# Audio-Beamformer_HDMI_V1_0.net
KiCad netlist of a schematic drawn in Altium Designer
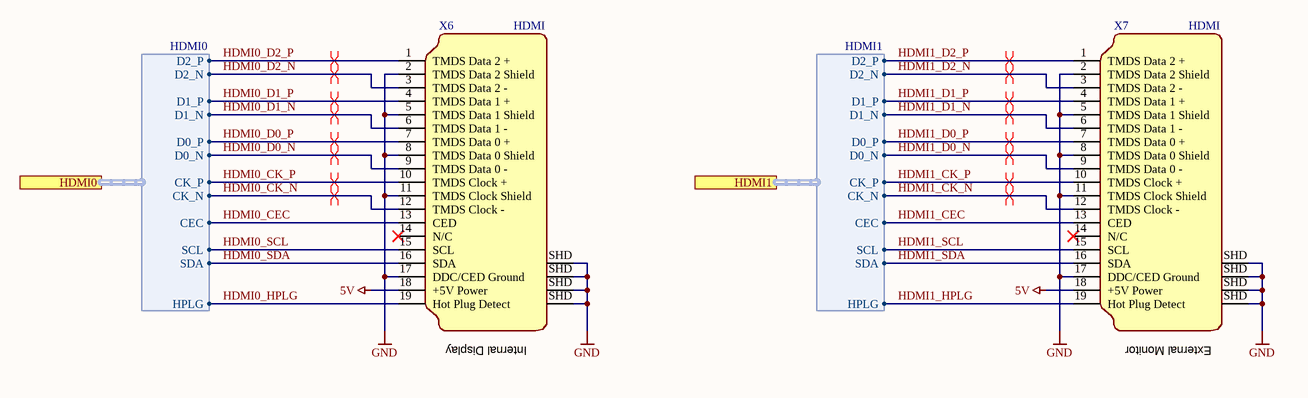
[diagram p0: Audio-Beamformer_HDMI_V1.0.SchDoc]

(export (version "E")
  (design (tool "Eeschema 10.0.6"))
  (components
    (comp (ref "X6")
      (value "HDMI")
      (footprint "SMD HDMI Horizontal")
      (description "Female Right Angle")
      (libsource (lib "Audio-Beamformer") (part "X-HDMI-Connector"))
    )
    (comp (ref "X7")
      (value "HDMI")
      (footprint "SMD HDMI Horizontal")
      (description "Female Right Angle")
      (libsource (lib "Audio-Beamformer") (part "X-HDMI-Connector"))
    )
  )
  (nets
    (net (code "3") (name "/HDMI0_CEC") (class "Default")
      (node (ref "X6") (pin "13") (pinfunction "CED_13") (pintype "passive"))
    )
    (net (code "4") (name "/HDMI0_CK_N") (class "Default")
      (node (ref "X6") (pin "12") (pinfunction "TMDS_Clock_-_12") (pintype "passive"))
    )
    (net (code "5") (name "/HDMI0_CK_P") (class "Default")
      (node (ref "X6") (pin "10") (pinfunction "TMDS_Clock_+_10") (pintype "passive"))
    )
    (net (code "6") (name "/HDMI0_D0_N") (class "Default")
      (node (ref "X6") (pin "9") (pinfunction "TMDS_Data_0_-_9") (pintype "passive"))
    )
    (net (code "7") (name "/HDMI0_D0_P") (class "Default")
      (node (ref "X6") (pin "7") (pinfunction "TMDS_Data_0_+_7") (pintype "passive"))
    )
    (net (code "8") (name "/HDMI0_D1_N") (class "Default")
      (node (ref "X6") (pin "6") (pinfunction "TMDS_Data_1_-_6") (pintype "passive"))
    )
    (net (code "9") (name "/HDMI0_D1_P") (class "Default")
      (node (ref "X6") (pin "4") (pinfunction "TMDS_Data_1_+_4") (pintype "passive"))
    )
    (net (code "10") (name "/HDMI0_D2_N") (class "Default")
      (node (ref "X6") (pin "3") (pinfunction "TMDS_Data_2_-_3") (pintype "passive"))
    )
    (net (code "11") (name "/HDMI0_D2_P") (class "Default")
      (node (ref "X6") (pin "1") (pinfunction "TMDS_Data_2_+_1") (pintype "passive"))
    )
    (net (code "12") (name "/HDMI0_HPLG") (class "Default")
      (node (ref "X6") (pin "19") (pinfunction "Hot_Plug_Detect_19") (pintype "passive"))
    )
    (net (code "13") (name "/HDMI0_SCL") (class "Default")
      (node (ref "X6") (pin "15") (pinfunction "SCL_15") (pintype "passive"))
    )
    (net (code "14") (name "/HDMI0_SDA") (class "Default")
      (node (ref "X6") (pin "16") (pinfunction "SDA_16") (pintype "passive"))
    )
    (net (code "15") (name "/HDMI1_CEC") (class "Default")
      (node (ref "X7") (pin "13") (pinfunction "CED_13") (pintype "passive"))
    )
    (net (code "16") (name "/HDMI1_CK_N") (class "Default")
      (node (ref "X7") (pin "12") (pinfunction "TMDS_Clock_-_12") (pintype "passive"))
    )
    (net (code "17") (name "/HDMI1_CK_P") (class "Default")
      (node (ref "X7") (pin "10") (pinfunction "TMDS_Clock_+_10") (pintype "passive"))
    )
    (net (code "18") (name "/HDMI1_D0_N") (class "Default")
      (node (ref "X7") (pin "9") (pinfunction "TMDS_Data_0_-_9") (pintype "passive"))
    )
    (net (code "19") (name "/HDMI1_D0_P") (class "Default")
      (node (ref "X7") (pin "7") (pinfunction "TMDS_Data_0_+_7") (pintype "passive"))
    )
    (net (code "20") (name "/HDMI1_D1_N") (class "Default")
      (node (ref "X7") (pin "6") (pinfunction "TMDS_Data_1_-_6") (pintype "passive"))
    )
    (net (code "21") (name "/HDMI1_D1_P") (class "Default")
      (node (ref "X7") (pin "4") (pinfunction "TMDS_Data_1_+_4") (pintype "passive"))
    )
    (net (code "22") (name "/HDMI1_D2_N") (class "Default")
      (node (ref "X7") (pin "3") (pinfunction "TMDS_Data_2_-_3") (pintype "passive"))
    )
    (net (code "23") (name "/HDMI1_D2_P") (class "Default")
      (node (ref "X7") (pin "1") (pinfunction "TMDS_Data_2_+_1") (pintype "passive"))
    )
    (net (code "24") (name "/HDMI1_HPLG") (class "Default")
      (node (ref "X7") (pin "19") (pinfunction "Hot_Plug_Detect_19") (pintype "passive"))
    )
    (net (code "25") (name "/HDMI1_SCL") (class "Default")
      (node (ref "X7") (pin "15") (pinfunction "SCL_15") (pintype "passive"))
    )
    (net (code "26") (name "/HDMI1_SDA") (class "Default")
      (node (ref "X7") (pin "16") (pinfunction "SDA_16") (pintype "passive"))
    )
    (net (code "29") (name "5V") (class "Default")
      (node (ref "X6") (pin "18") (pinfunction "+5V_Power_18") (pintype "passive"))
      (node (ref "X7") (pin "18") (pinfunction "+5V_Power_18") (pintype "passive"))
    )
    (net (code "30") (name "GND") (class "Default")
      (node (ref "X6") (pin "11") (pinfunction "TMDS_Clock_Shield_11") (pintype "passive"))
      (node (ref "X6") (pin "17") (pinfunction "DDC/CED_Ground_17") (pintype "passive"))
      (node (ref "X6") (pin "2") (pinfunction "TMDS_Data_2_Shield_2") (pintype "passive"))
      (node (ref "X6") (pin "5") (pinfunction "TMDS_Data_1_Shield_5") (pintype "passive"))
      (node (ref "X6") (pin "8") (pinfunction "TMDS_Data_0_Shield_8") (pintype "passive"))
      (node (ref "X6") (pin "SHD") (pinfunction "SHD_SHD") (pintype "passive"))
      (node (ref "X7") (pin "11") (pinfunction "TMDS_Clock_Shield_11") (pintype "passive"))
      (node (ref "X7") (pin "17") (pinfunction "DDC/CED_Ground_17") (pintype "passive"))
      (node (ref "X7") (pin "2") (pinfunction "TMDS_Data_2_Shield_2") (pintype "passive"))
      (node (ref "X7") (pin "5") (pinfunction "TMDS_Data_1_Shield_5") (pintype "passive"))
      (node (ref "X7") (pin "8") (pinfunction "TMDS_Data_0_Shield_8") (pintype "passive"))
      (node (ref "X7") (pin "SHD") (pinfunction "SHD_SHD") (pintype "passive"))
    )
    (net (code "31") (name "unconnected-(X6-N{slash}C-Pad14)") (class "Default")
      (node (ref "X6") (pin "14") (pinfunction "N/C_14") (pintype "passive+no_connect"))
    )
    (net (code "32") (name "unconnected-(X7-N{slash}C-Pad14)") (class "Default")
      (node (ref "X7") (pin "14") (pinfunction "N/C_14") (pintype "passive+no_connect"))
    )
  )
)
